# L293_large.net
KiCad netlist of a schematic drawn in EAGLE
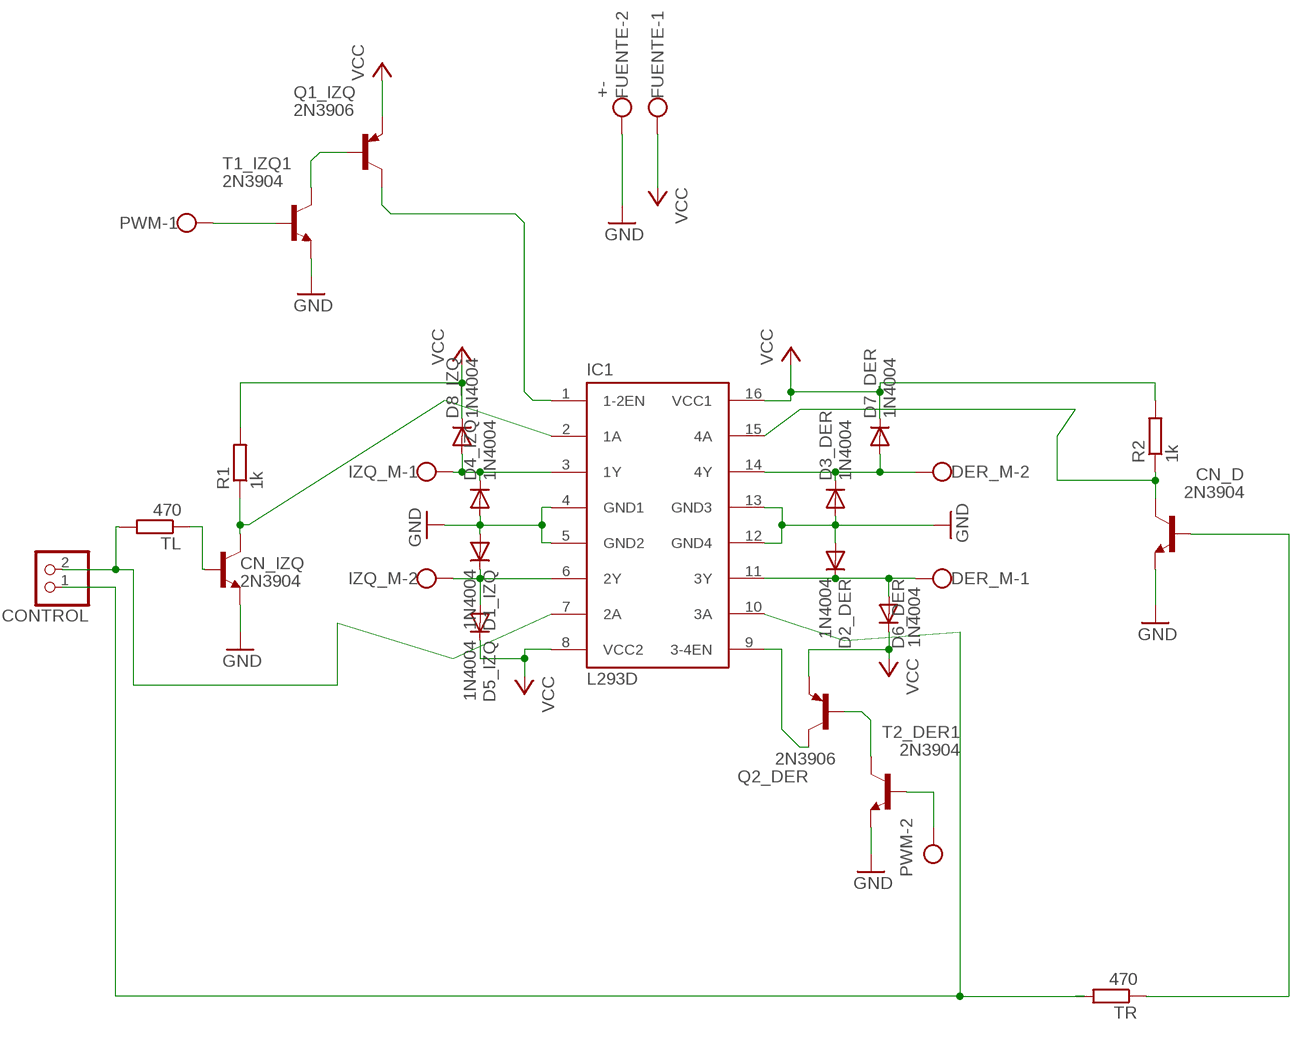
[diagram p0: schematic, sheet 1]

(export (version "E")
  (design (tool "Eeschema 10.0.6"))
  (components
    (comp (ref "CN_D")
      (value "2N3904")
      (footprint "eagle-import:TO92")
      (libsource (lib "eagle-import") (part "2N3904"))
    )
    (comp (ref "CN_IZQ")
      (value "2N3904")
      (footprint "eagle-import:TO92")
      (libsource (lib "eagle-import") (part "2N3904"))
    )
    (comp (ref "CONTROL")
      (value "PINHD-1X2/90")
      (footprint "eagle-import:1X02_90")
      (libsource (lib "eagle-import") (part "PINHD-1X2/90"))
    )
    (comp (ref "D1_IZQ")
      (value "1N4004")
      (footprint "eagle-import:DO41-10")
      (libsource (lib "eagle-import") (part "1N4004"))
    )
    (comp (ref "D2_DER")
      (value "1N4004")
      (footprint "eagle-import:DO41-10")
      (libsource (lib "eagle-import") (part "1N4004"))
    )
    (comp (ref "D3_DER")
      (value "1N4004")
      (footprint "eagle-import:DO41-10")
      (libsource (lib "eagle-import") (part "1N4004"))
    )
    (comp (ref "D4_IZQ")
      (value "1N4004")
      (footprint "eagle-import:DO41-10")
      (libsource (lib "eagle-import") (part "1N4004"))
    )
    (comp (ref "D5_IZQ")
      (value "1N4004")
      (footprint "eagle-import:DO41-10")
      (libsource (lib "eagle-import") (part "1N4004"))
    )
    (comp (ref "D6_DER")
      (value "1N4004")
      (footprint "eagle-import:DO41-10")
      (libsource (lib "eagle-import") (part "1N4004"))
    )
    (comp (ref "D7_DER")
      (value "1N4004")
      (footprint "eagle-import:DO41-10")
      (libsource (lib "eagle-import") (part "1N4004"))
    )
    (comp (ref "D8_IZQ")
      (value "1N4004")
      (footprint "eagle-import:DO41-10")
      (libsource (lib "eagle-import") (part "1N4004"))
    )
    (comp (ref "DER_M")
      (value "W237-02P")
      (footprint "eagle-import:W237-132")
      (libsource (lib "eagle-import") (part "W237-02P"))
    )
    (comp (ref "FUENTE")
      (value "+-")
      (footprint "eagle-import:W237-132")
      (libsource (lib "eagle-import") (part "W237-02P"))
    )
    (comp (ref "IC1")
      (value "L293D")
      (footprint "eagle-import:DIL16")
      (libsource (lib "eagle-import") (part "L293D"))
    )
    (comp (ref "IZQ_M")
      (value "W237-02P")
      (footprint "eagle-import:W237-132")
      (libsource (lib "eagle-import") (part "W237-02P"))
    )
    (comp (ref "PWM")
      (value "W237-02P")
      (footprint "eagle-import:W237-132")
      (libsource (lib "eagle-import") (part "W237-02P"))
    )
    (comp (ref "Q1_IZQ")
      (value "2N3906")
      (footprint "eagle-import:TO92")
      (libsource (lib "eagle-import") (part "2N3906"))
    )
    (comp (ref "Q2_DER")
      (value "2N3906")
      (footprint "eagle-import:TO92")
      (libsource (lib "eagle-import") (part "2N3906"))
    )
    (comp (ref "R1")
      (value "1k")
      (footprint "eagle-import:0207_5V")
      (libsource (lib "eagle-import") (part "R-EU_0207/5V"))
    )
    (comp (ref "R2")
      (value "1k")
      (footprint "eagle-import:0207_5V")
      (libsource (lib "eagle-import") (part "R-EU_0207/5V"))
    )
    (comp (ref "T1_IZQ1")
      (value "2N3904")
      (footprint "eagle-import:TO92")
      (libsource (lib "eagle-import") (part "2N3904"))
    )
    (comp (ref "T2_DER1")
      (value "2N3904")
      (footprint "eagle-import:TO92")
      (libsource (lib "eagle-import") (part "2N3904"))
    )
    (comp (ref "TL")
      (value "470")
      (footprint "eagle-import:0207_5V")
      (libsource (lib "eagle-import") (part "R-EU_0207/5V"))
    )
    (comp (ref "TR")
      (value "470")
      (footprint "eagle-import:0207_5V")
      (libsource (lib "eagle-import") (part "R-EU_0207/5V"))
    )
  )
  (nets
    (net (code "1") (name "GND") (class "Default")
      (node (ref "CN_D") (pin "3") (pinfunction "E_3") (pintype "passive"))
      (node (ref "CN_IZQ") (pin "3") (pinfunction "E_3") (pintype "passive"))
      (node (ref "D1_IZQ") (pin "A") (pinfunction "A_A") (pintype "passive"))
      (node (ref "D2_DER") (pin "A") (pinfunction "A_A") (pintype "passive"))
      (node (ref "D3_DER") (pin "A") (pinfunction "A_A") (pintype "passive"))
      (node (ref "D4_IZQ") (pin "A") (pinfunction "A_A") (pintype "passive"))
      (node (ref "FUENTE") (pin "2") (pinfunction "KL_2") (pintype "passive"))
      (node (ref "IC1") (pin "12") (pinfunction "GND4_12") (pintype "power_in"))
      (node (ref "IC1") (pin "13") (pinfunction "GND3_13") (pintype "power_in"))
      (node (ref "IC1") (pin "4") (pinfunction "GND1_4") (pintype "power_in"))
      (node (ref "IC1") (pin "5") (pinfunction "GND2_5") (pintype "power_in"))
      (node (ref "T1_IZQ1") (pin "3") (pinfunction "E_3") (pintype "passive"))
      (node (ref "T2_DER1") (pin "3") (pinfunction "E_3") (pintype "passive"))
    )
    (net (code "2") (name "Net-(CN_D-B)") (class "Default")
      (node (ref "CN_D") (pin "2") (pinfunction "B_2") (pintype "passive"))
      (node (ref "TR") (pin "1") (pinfunction "1_1") (pintype "passive"))
    )
    (net (code "3") (name "Net-(CN_D-C)") (class "Default")
      (node (ref "CN_D") (pin "1") (pinfunction "C_1") (pintype "passive"))
      (node (ref "IC1") (pin "15") (pinfunction "4A_15") (pintype "input"))
      (node (ref "R2") (pin "1") (pinfunction "1_1") (pintype "passive"))
    )
    (net (code "4") (name "Net-(CN_IZQ-B)") (class "Default")
      (node (ref "CN_IZQ") (pin "2") (pinfunction "B_2") (pintype "passive"))
      (node (ref "TL") (pin "1") (pinfunction "1_1") (pintype "passive"))
    )
    (net (code "5") (name "Net-(CN_IZQ-C)") (class "Default")
      (node (ref "CN_IZQ") (pin "1") (pinfunction "C_1") (pintype "passive"))
      (node (ref "IC1") (pin "2") (pinfunction "1A_2") (pintype "input"))
      (node (ref "R1") (pin "1") (pinfunction "1_1") (pintype "passive"))
    )
    (net (code "6") (name "Net-(DER_MA-KL)") (class "Default")
      (node (ref "D2_DER") (pin "C") (pinfunction "C_C") (pintype "passive"))
      (node (ref "D6_DER") (pin "A") (pinfunction "A_A") (pintype "passive"))
      (node (ref "DER_M") (pin "1") (pinfunction "KL_1") (pintype "passive"))
      (node (ref "IC1") (pin "11") (pinfunction "3Y_11") (pintype "output"))
    )
    (net (code "7") (name "Net-(DER_MB-KL)") (class "Default")
      (node (ref "D3_DER") (pin "C") (pinfunction "C_C") (pintype "passive"))
      (node (ref "D7_DER") (pin "A") (pinfunction "A_A") (pintype "passive"))
      (node (ref "DER_M") (pin "2") (pinfunction "KL_2") (pintype "passive"))
      (node (ref "IC1") (pin "14") (pinfunction "4Y_14") (pintype "output"))
    )
    (net (code "8") (name "Net-(IC1-1-2EN)") (class "Default")
      (node (ref "IC1") (pin "1") (pinfunction "1-2EN_1") (pintype "input"))
      (node (ref "Q1_IZQ") (pin "1") (pinfunction "C_1") (pintype "passive"))
    )
    (net (code "9") (name "Net-(IC1-1Y)") (class "Default")
      (node (ref "D4_IZQ") (pin "C") (pinfunction "C_C") (pintype "passive"))
      (node (ref "D8_IZQ") (pin "A") (pinfunction "A_A") (pintype "passive"))
      (node (ref "IC1") (pin "3") (pinfunction "1Y_3") (pintype "output"))
      (node (ref "IZQ_M") (pin "1") (pinfunction "KL_1") (pintype "passive"))
    )
    (net (code "10") (name "Net-(IC1-2A)") (class "Default")
      (node (ref "CONTROL") (pin "2") (pinfunction "2_2") (pintype "passive"))
      (node (ref "IC1") (pin "7") (pinfunction "2A_7") (pintype "input"))
      (node (ref "TL") (pin "2") (pinfunction "2_2") (pintype "passive"))
    )
    (net (code "11") (name "Net-(IC1-2Y)") (class "Default")
      (node (ref "D1_IZQ") (pin "C") (pinfunction "C_C") (pintype "passive"))
      (node (ref "D5_IZQ") (pin "A") (pinfunction "A_A") (pintype "passive"))
      (node (ref "IC1") (pin "6") (pinfunction "2Y_6") (pintype "output"))
      (node (ref "IZQ_M") (pin "2") (pinfunction "KL_2") (pintype "passive"))
    )
    (net (code "12") (name "Net-(IC1-3-4EN)") (class "Default")
      (node (ref "IC1") (pin "9") (pinfunction "3-4EN_9") (pintype "input"))
      (node (ref "Q2_DER") (pin "1") (pinfunction "C_1") (pintype "passive"))
    )
    (net (code "13") (name "Net-(IC1-3A)") (class "Default")
      (node (ref "CONTROL") (pin "1") (pinfunction "1_1") (pintype "passive"))
      (node (ref "IC1") (pin "10") (pinfunction "3A_10") (pintype "input"))
      (node (ref "TR") (pin "2") (pinfunction "2_2") (pintype "passive"))
    )
    (net (code "14") (name "Net-(PWMA-KL)") (class "Default")
      (node (ref "PWM") (pin "1") (pinfunction "KL_1") (pintype "passive"))
      (node (ref "T1_IZQ1") (pin "2") (pinfunction "B_2") (pintype "passive"))
    )
    (net (code "15") (name "Net-(PWMB-KL)") (class "Default")
      (node (ref "PWM") (pin "2") (pinfunction "KL_2") (pintype "passive"))
      (node (ref "T2_DER1") (pin "2") (pinfunction "B_2") (pintype "passive"))
    )
    (net (code "16") (name "Net-(Q1_IZQ-B)") (class "Default")
      (node (ref "Q1_IZQ") (pin "2") (pinfunction "B_2") (pintype "passive"))
      (node (ref "T1_IZQ1") (pin "1") (pinfunction "C_1") (pintype "passive"))
    )
    (net (code "17") (name "Net-(Q2_DER-B)") (class "Default")
      (node (ref "Q2_DER") (pin "2") (pinfunction "B_2") (pintype "passive"))
      (node (ref "T2_DER1") (pin "1") (pinfunction "C_1") (pintype "passive"))
    )
    (net (code "18") (name "VCC") (class "Default")
      (node (ref "D5_IZQ") (pin "C") (pinfunction "C_C") (pintype "passive"))
      (node (ref "D6_DER") (pin "C") (pinfunction "C_C") (pintype "passive"))
      (node (ref "D7_DER") (pin "C") (pinfunction "C_C") (pintype "passive"))
      (node (ref "D8_IZQ") (pin "C") (pinfunction "C_C") (pintype "passive"))
      (node (ref "FUENTE") (pin "1") (pinfunction "KL_1") (pintype "passive"))
      (node (ref "IC1") (pin "16") (pinfunction "VCC1_16") (pintype "power_in"))
      (node (ref "IC1") (pin "8") (pinfunction "VCC2_8") (pintype "power_in"))
      (node (ref "Q1_IZQ") (pin "3") (pinfunction "E_3") (pintype "passive"))
      (node (ref "Q2_DER") (pin "3") (pinfunction "E_3") (pintype "passive"))
      (node (ref "R1") (pin "2") (pinfunction "2_2") (pintype "passive"))
      (node (ref "R2") (pin "2") (pinfunction "2_2") (pintype "passive"))
    )
  )
)
